# AS3935-EV.net
KiCad netlist of a schematic drawn in EAGLE
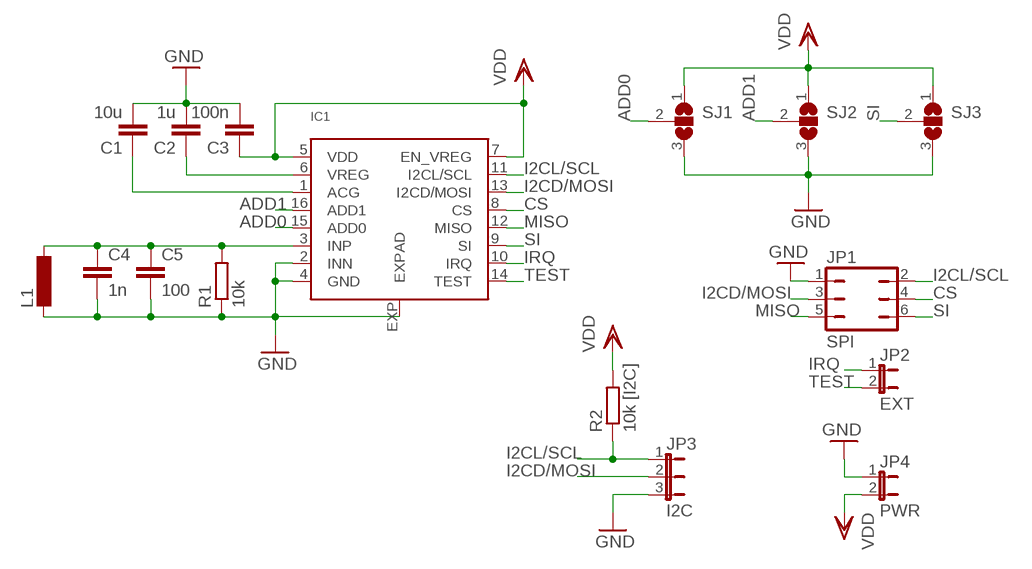
[diagram p0: schematic, sheet 1]

(export (version "E")
  (design (tool "Eeschema 10.0.6"))
  (components
    (comp (ref "C1")
      (value "10u")
      (footprint "eagle-import:C0805")
      (libsource (lib "eagle-import") (part "C-EUC0805"))
    )
    (comp (ref "C2")
      (value "1u")
      (footprint "eagle-import:C0805")
      (libsource (lib "eagle-import") (part "C-EUC0805"))
    )
    (comp (ref "C3")
      (value "100n")
      (footprint "eagle-import:C0603")
      (libsource (lib "eagle-import") (part "C-EUC0603"))
    )
    (comp (ref "C4")
      (value "1n")
      (footprint "eagle-import:C0603")
      (libsource (lib "eagle-import") (part "C-EUC0603"))
    )
    (comp (ref "C5")
      (value "100")
      (footprint "eagle-import:C0603")
      (libsource (lib "eagle-import") (part "C-EUC0603"))
    )
    (comp (ref "IC1")
      (value "AS3935")
      (footprint "eagle-import:16LDMLPQ")
      (libsource (lib "eagle-import") (part "AS3935"))
    )
    (comp (ref "JP1")
      (value "SPI")
      (footprint "eagle-import:JP3Q")
      (libsource (lib "eagle-import") (part "JP3Q"))
    )
    (comp (ref "JP2")
      (value "EXT")
      (footprint "eagle-import:JP1")
      (libsource (lib "eagle-import") (part "JP1E"))
    )
    (comp (ref "JP3")
      (value "I2C")
      (footprint "eagle-import:JP2")
      (libsource (lib "eagle-import") (part "JP2E"))
    )
    (comp (ref "JP4")
      (value "PWR")
      (footprint "eagle-import:JP1")
      (libsource (lib "eagle-import") (part "JP1E"))
    )
    (comp (ref "L1")
      (value "COILCRAFT")
      (footprint "eagle-import:COILCRAFT")
      (libsource (lib "eagle-import") (part "COILCRAFT"))
    )
    (comp (ref "R1")
      (value "10k")
      (footprint "eagle-import:R0603")
      (libsource (lib "eagle-import") (part "R-EU_R0603"))
    )
    (comp (ref "R2")
      (value "10k [I2C]")
      (footprint "eagle-import:R0603")
      (libsource (lib "eagle-import") (part "R-EU_R0603"))
    )
    (comp (ref "SJ1")
      (value "SJ2W")
      (footprint "eagle-import:SJ_2")
      (libsource (lib "eagle-import") (part "SJ2W"))
    )
    (comp (ref "SJ2")
      (value "SJ2W")
      (footprint "eagle-import:SJ_2")
      (libsource (lib "eagle-import") (part "SJ2W"))
    )
    (comp (ref "SJ3")
      (value "SJ2W")
      (footprint "eagle-import:SJ_2")
      (libsource (lib "eagle-import") (part "SJ2W"))
    )
  )
  (nets
    (net (code "1") (name "/ADD0") (class "Default")
      (node (ref "IC1") (pin "15") (pinfunction "ADD0_15") (pintype "bidirectional"))
      (node (ref "SJ1") (pin "2") (pinfunction "2_2") (pintype "passive"))
    )
    (net (code "2") (name "/ADD1") (class "Default")
      (node (ref "IC1") (pin "16") (pinfunction "ADD1_16") (pintype "bidirectional"))
      (node (ref "SJ2") (pin "2") (pinfunction "2_2") (pintype "passive"))
    )
    (net (code "3") (name "/CS") (class "Default")
      (node (ref "IC1") (pin "8") (pinfunction "CS_8") (pintype "bidirectional"))
      (node (ref "JP1") (pin "4") (pinfunction "4_4") (pintype "passive"))
    )
    (net (code "4") (name "/I2CD{slash}MOSI") (class "Default")
      (node (ref "IC1") (pin "13") (pinfunction "I2CD/MOSI_13") (pintype "bidirectional"))
      (node (ref "JP1") (pin "3") (pinfunction "3_3") (pintype "passive"))
      (node (ref "JP3") (pin "2") (pinfunction "2_2") (pintype "passive"))
    )
    (net (code "5") (name "/I2CL{slash}SCL") (class "Default")
      (node (ref "IC1") (pin "11") (pinfunction "I2CL/SCL_11") (pintype "bidirectional"))
      (node (ref "JP1") (pin "2") (pinfunction "2_2") (pintype "passive"))
      (node (ref "JP3") (pin "1") (pinfunction "1_1") (pintype "passive"))
      (node (ref "R2") (pin "1") (pinfunction "1_1") (pintype "passive"))
    )
    (net (code "6") (name "/IRQ") (class "Default")
      (node (ref "IC1") (pin "10") (pinfunction "IRQ_10") (pintype "bidirectional"))
      (node (ref "JP2") (pin "1") (pinfunction "1_1") (pintype "passive"))
    )
    (net (code "7") (name "/MISO") (class "Default")
      (node (ref "IC1") (pin "12") (pinfunction "MISO_12") (pintype "bidirectional"))
      (node (ref "JP1") (pin "5") (pinfunction "5_5") (pintype "passive"))
    )
    (net (code "8") (name "/SI") (class "Default")
      (node (ref "IC1") (pin "9") (pinfunction "SI_9") (pintype "bidirectional"))
      (node (ref "JP1") (pin "6") (pinfunction "6_6") (pintype "passive"))
      (node (ref "SJ3") (pin "2") (pinfunction "2_2") (pintype "passive"))
    )
    (net (code "9") (name "/TEST") (class "Default")
      (node (ref "IC1") (pin "14") (pinfunction "TEST_14") (pintype "passive"))
      (node (ref "JP2") (pin "2") (pinfunction "2_2") (pintype "passive"))
    )
    (net (code "10") (name "GND") (class "Default")
      (node (ref "C1") (pin "2") (pinfunction "2_2") (pintype "passive"))
      (node (ref "C2") (pin "2") (pinfunction "2_2") (pintype "passive"))
      (node (ref "C3") (pin "2") (pinfunction "2_2") (pintype "passive"))
      (node (ref "C4") (pin "2") (pinfunction "2_2") (pintype "passive"))
      (node (ref "C5") (pin "2") (pinfunction "2_2") (pintype "passive"))
      (node (ref "IC1") (pin "2") (pinfunction "INN_2") (pintype "bidirectional"))
      (node (ref "IC1") (pin "4") (pinfunction "GND_4") (pintype "bidirectional"))
      (node (ref "IC1") (pin "EXP") (pinfunction "EXPAD_EXP") (pintype "bidirectional"))
      (node (ref "JP1") (pin "1") (pinfunction "1_1") (pintype "passive"))
      (node (ref "JP3") (pin "3") (pinfunction "3_3") (pintype "passive"))
      (node (ref "JP4") (pin "1") (pinfunction "1_1") (pintype "passive"))
      (node (ref "L1") (pin "2") (pinfunction "2_2") (pintype "passive"))
      (node (ref "R1") (pin "1") (pinfunction "1_1") (pintype "passive"))
      (node (ref "SJ1") (pin "3") (pinfunction "3_3") (pintype "passive"))
      (node (ref "SJ2") (pin "3") (pinfunction "3_3") (pintype "passive"))
      (node (ref "SJ3") (pin "3") (pinfunction "3_3") (pintype "passive"))
    )
    (net (code "11") (name "Net-(IC1-ACG)") (class "Default")
      (node (ref "C1") (pin "1") (pinfunction "1_1") (pintype "passive"))
      (node (ref "IC1") (pin "1") (pinfunction "ACG_1") (pintype "bidirectional"))
    )
    (net (code "12") (name "Net-(IC1-INP)") (class "Default")
      (node (ref "C4") (pin "1") (pinfunction "1_1") (pintype "passive"))
      (node (ref "C5") (pin "1") (pinfunction "1_1") (pintype "passive"))
      (node (ref "IC1") (pin "3") (pinfunction "INP_3") (pintype "bidirectional"))
      (node (ref "L1") (pin "1") (pinfunction "1_1") (pintype "passive"))
      (node (ref "R1") (pin "2") (pinfunction "2_2") (pintype "passive"))
    )
    (net (code "13") (name "Net-(IC1-VREG)") (class "Default")
      (node (ref "C2") (pin "1") (pinfunction "1_1") (pintype "passive"))
      (node (ref "IC1") (pin "6") (pinfunction "VREG_6") (pintype "bidirectional"))
    )
    (net (code "14") (name "VDD") (class "Default")
      (node (ref "C3") (pin "1") (pinfunction "1_1") (pintype "passive"))
      (node (ref "IC1") (pin "5") (pinfunction "VDD_5") (pintype "bidirectional"))
      (node (ref "IC1") (pin "7") (pinfunction "EN_VREG_7") (pintype "bidirectional"))
      (node (ref "JP4") (pin "2") (pinfunction "2_2") (pintype "passive"))
      (node (ref "R2") (pin "2") (pinfunction "2_2") (pintype "passive"))
      (node (ref "SJ1") (pin "1") (pinfunction "1_1") (pintype "passive"))
      (node (ref "SJ2") (pin "1") (pinfunction "1_1") (pintype "passive"))
      (node (ref "SJ3") (pin "1") (pinfunction "1_1") (pintype "passive"))
    )
  )
)
